# base.net
KiCad netlist of a schematic drawn in EAGLE
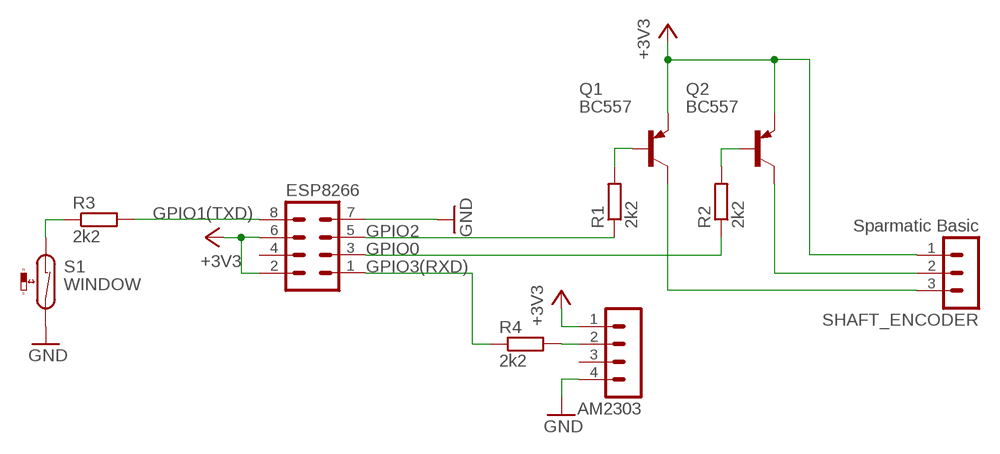
[diagram p0: schematic, sheet 1]

(export (version "E")
  (design (tool "Eeschema 10.0.6"))
  (components
    (comp (ref "AM2303")
      (value "MA04-1")
      (footprint "eagle-import:MA04-1")
      (libsource (lib "eagle-import") (part "MA04-1"))
    )
    (comp (ref "ESP8266")
      (value "MA04-2")
      (footprint "eagle-import:MA04-2")
      (libsource (lib "eagle-import") (part "MA04-2"))
    )
    (comp (ref "Q1")
      (value "BC557")
      (footprint "eagle-import:TO92-EBC")
      (libsource (lib "eagle-import") (part "BC557"))
    )
    (comp (ref "Q2")
      (value "BC557")
      (footprint "eagle-import:TO92-EBC")
      (libsource (lib "eagle-import") (part "BC557"))
    )
    (comp (ref "R1")
      (value "2k2")
      (footprint "eagle-import:0204_7")
      (libsource (lib "eagle-import") (part "R-EU_0204/7"))
    )
    (comp (ref "R2")
      (value "2k2")
      (footprint "eagle-import:0204_7")
      (libsource (lib "eagle-import") (part "R-EU_0204/7"))
    )
    (comp (ref "R3")
      (value "2k2")
      (footprint "eagle-import:0204_7")
      (libsource (lib "eagle-import") (part "R-EU_0204/7"))
    )
    (comp (ref "R4")
      (value "2k2")
      (footprint "eagle-import:0204_7")
      (libsource (lib "eagle-import") (part "R-EU_0204/7"))
    )
    (comp (ref "S1")
      (value "WINDOW")
      (footprint "eagle-import:MK6-8-A")
      (fields (field (name "MF") "MEDER") (field (name "MPN") "MK6-8-H"))
      (libsource (lib "eagle-import") (part "REED-SWITCH-MK6-8-H"))
    )
    (comp (ref "SHAFT_ENCODER")
      (value "Sparmatic Basic")
      (footprint "eagle-import:MA03-1")
      (libsource (lib "eagle-import") (part "MA03-1"))
    )
  )
  (nets
    (net (code "1") (name "+3V3") (class "Default")
      (node (ref "AM2303") (pin "1") (pinfunction "1_1") (pintype "passive"))
      (node (ref "ESP8266") (pin "2") (pinfunction "2_2") (pintype "passive"))
      (node (ref "ESP8266") (pin "6") (pinfunction "6_6") (pintype "passive"))
      (node (ref "Q1") (pin "E") (pinfunction "E_E") (pintype "passive"))
      (node (ref "Q2") (pin "E") (pinfunction "E_E") (pintype "passive"))
      (node (ref "SHAFT_ENCODER") (pin "1") (pinfunction "1_1") (pintype "passive"))
    )
    (net (code "2") (name "/GPIO0") (class "Default")
      (node (ref "ESP8266") (pin "3") (pinfunction "3_3") (pintype "passive"))
      (node (ref "R2") (pin "1") (pinfunction "1_1") (pintype "passive"))
    )
    (net (code "3") (name "/GPIO1(TXD)") (class "Default")
      (node (ref "ESP8266") (pin "8") (pinfunction "8_8") (pintype "passive"))
      (node (ref "R3") (pin "2") (pinfunction "2_2") (pintype "passive"))
    )
    (net (code "4") (name "/GPIO2") (class "Default")
      (node (ref "ESP8266") (pin "5") (pinfunction "5_5") (pintype "passive"))
      (node (ref "R1") (pin "1") (pinfunction "1_1") (pintype "passive"))
    )
    (net (code "5") (name "/GPIO3(RXD)") (class "Default")
      (node (ref "ESP8266") (pin "1") (pinfunction "1_1") (pintype "passive"))
      (node (ref "R4") (pin "1") (pinfunction "1_1") (pintype "passive"))
    )
    (net (code "6") (name "GND") (class "Default")
      (node (ref "AM2303") (pin "4") (pinfunction "4_4") (pintype "passive"))
      (node (ref "ESP8266") (pin "7") (pinfunction "7_7") (pintype "passive"))
      (node (ref "S1") (pin "2") (pinfunction "2_2") (pintype "passive"))
    )
    (net (code "7") (name "Net-(AM2303-Pad2)") (class "Default")
      (node (ref "AM2303") (pin "2") (pinfunction "2_2") (pintype "passive"))
      (node (ref "R4") (pin "2") (pinfunction "2_2") (pintype "passive"))
    )
    (net (code "8") (name "Net-(Q1-PadB)") (class "Default")
      (node (ref "Q1") (pin "B") (pinfunction "B_B") (pintype "passive"))
      (node (ref "R1") (pin "2") (pinfunction "2_2") (pintype "passive"))
    )
    (net (code "9") (name "Net-(Q1-PadC)") (class "Default")
      (node (ref "Q1") (pin "C") (pinfunction "C_C") (pintype "passive"))
      (node (ref "SHAFT_ENCODER") (pin "3") (pinfunction "3_3") (pintype "passive"))
    )
    (net (code "10") (name "Net-(Q2-PadB)") (class "Default")
      (node (ref "Q2") (pin "B") (pinfunction "B_B") (pintype "passive"))
      (node (ref "R2") (pin "2") (pinfunction "2_2") (pintype "passive"))
    )
    (net (code "11") (name "Net-(Q2-PadC)") (class "Default")
      (node (ref "Q2") (pin "C") (pinfunction "C_C") (pintype "passive"))
      (node (ref "SHAFT_ENCODER") (pin "2") (pinfunction "2_2") (pintype "passive"))
    )
    (net (code "12") (name "Net-(R3-Pad1)") (class "Default")
      (node (ref "R3") (pin "1") (pinfunction "1_1") (pintype "passive"))
      (node (ref "S1") (pin "1") (pinfunction "1_1") (pintype "passive"))
    )
    (net (code "13") (name "unconnected-(AM2303-Pad3)") (class "Default")
      (node (ref "AM2303") (pin "3") (pinfunction "3_3") (pintype "passive"))
    )
    (net (code "14") (name "unconnected-(ESP8266-Pad4)") (class "Default")
      (node (ref "ESP8266") (pin "4") (pinfunction "4_4") (pintype "passive"))
    )
  )
)
